# MotherBoard.net
KiCad netlist of a schematic drawn in Altium Designer
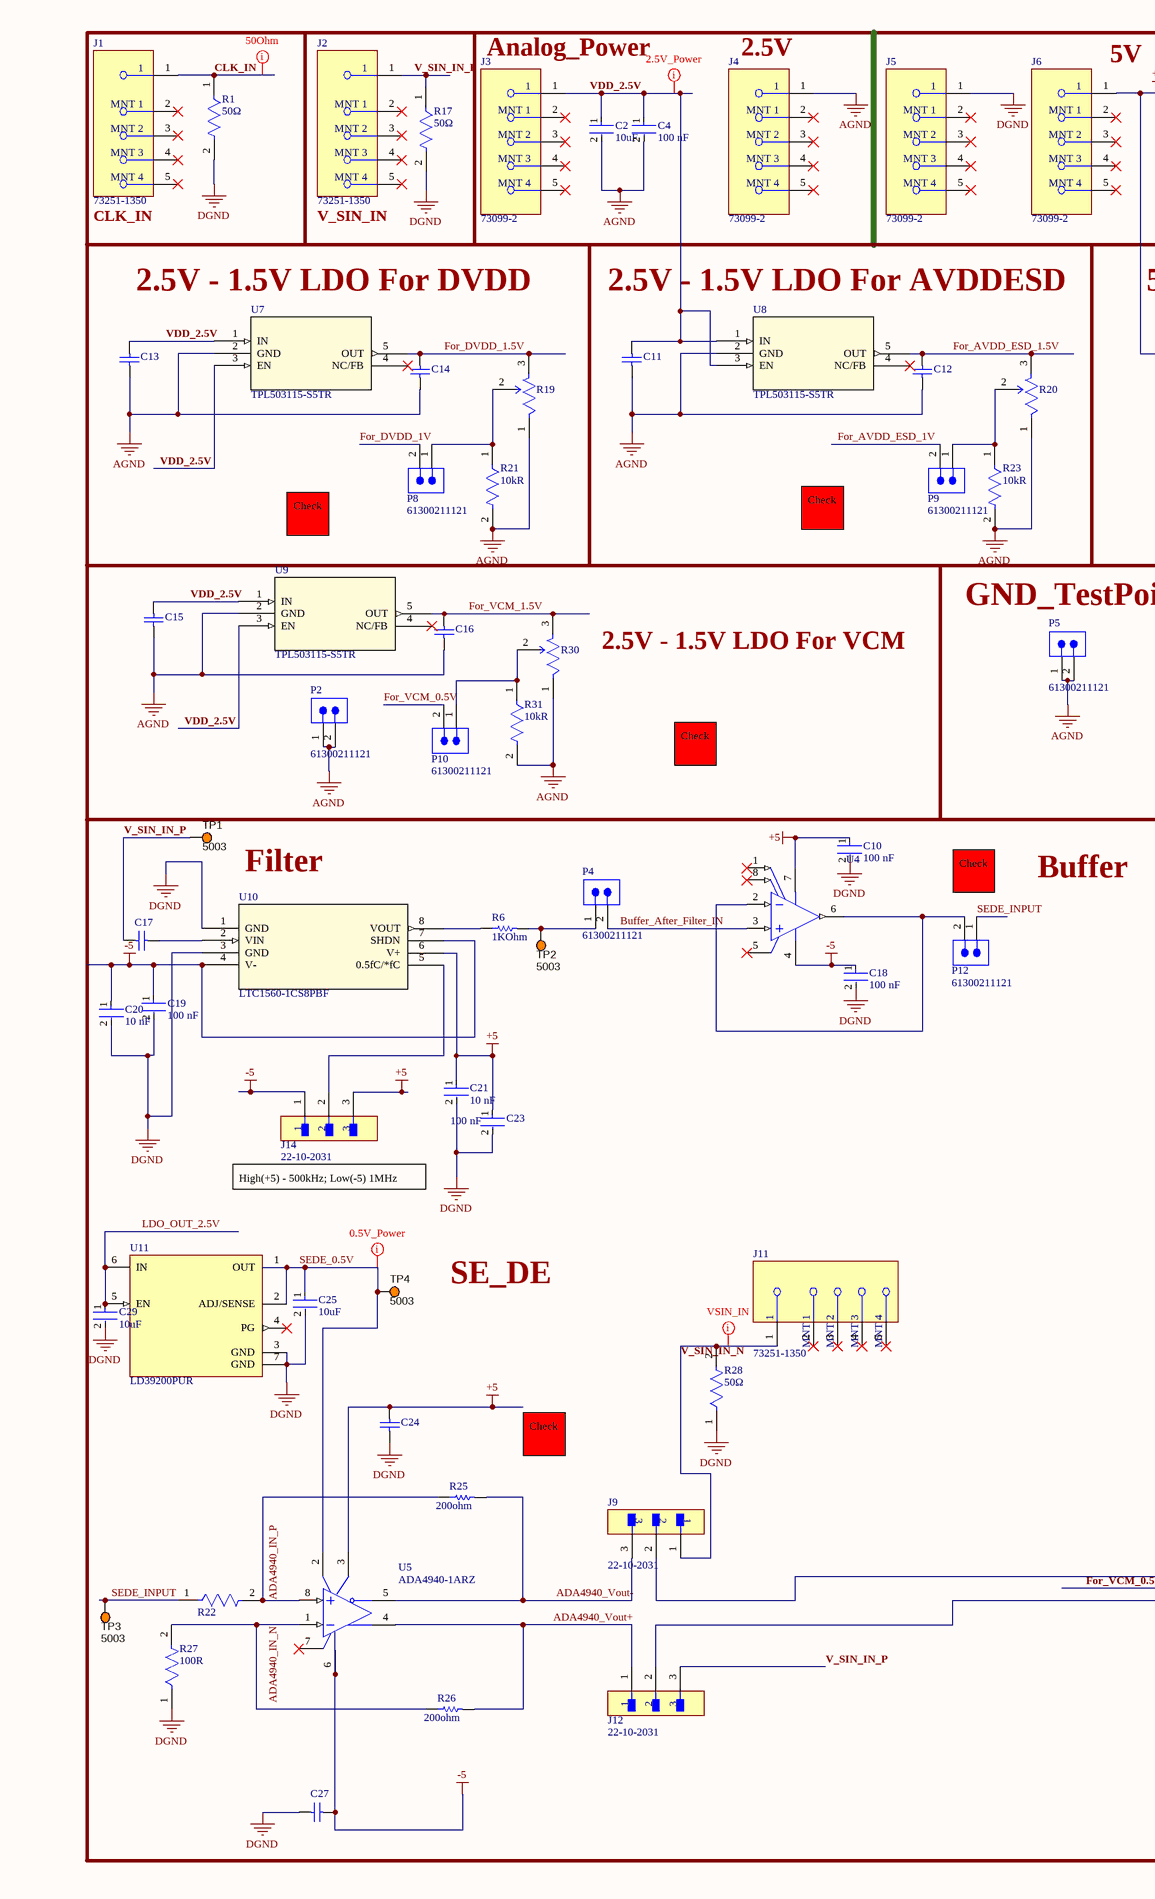
[diagram p0: MotherBoard.SchDoc, left]
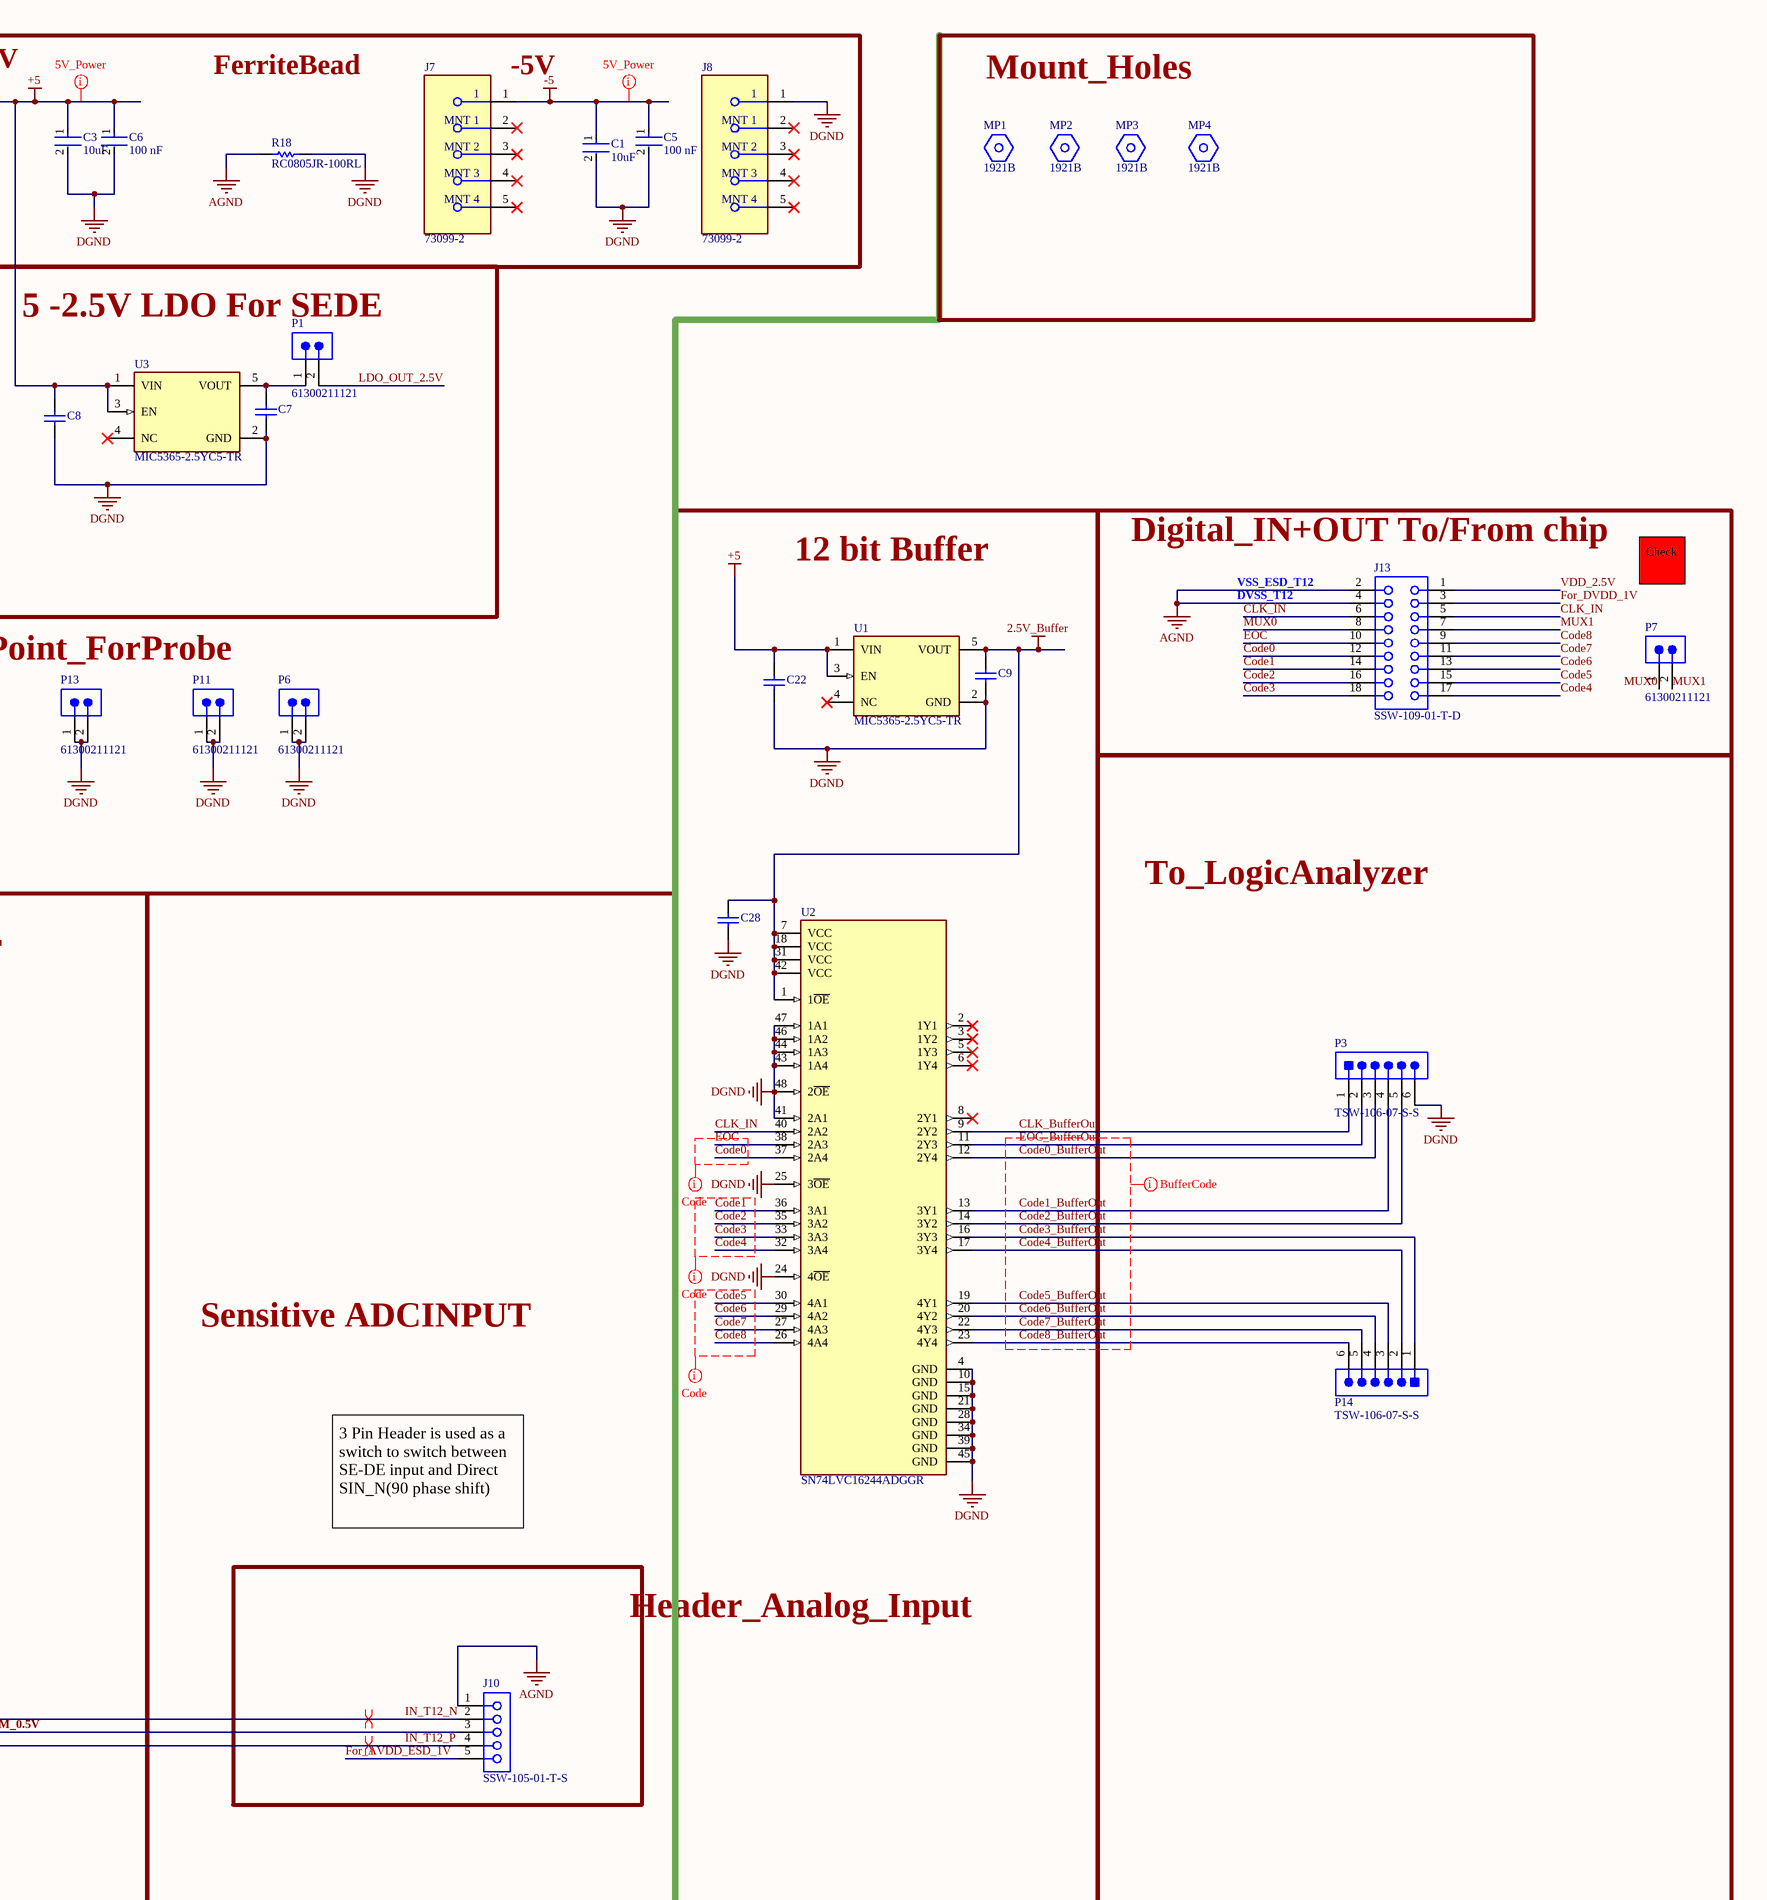
[diagram p1: MotherBoard.SchDoc, right]

(export (version "E")
  (design (tool "Eeschema 10.0.6"))
  (components
    (comp (ref "C1")
      (value "0805ZD106MAT2A")
      (footprint "FP-0805-L_2_01_0_2-W_1_25-MFG")
      (description "General Purpose Ceramic Capacitor, 0805, 10uF, 20%, X5R, 15%, 10V")
      (fields
        (field (name "CAPACITANCE") "10uF")
        (field (name "TOLERANCE") "20%")
        (field (name "VOLTAGE") "10V")
      )
      (libsource (lib "Altium Content Vault") (part "02cd4be3c70576c341d710602a673aa"))
    )
    (comp (ref "C2")
      (value "0805ZD106MAT2A")
      (footprint "FP-0805-L_2_01_0_2-W_1_25-MFG")
      (description "General Purpose Ceramic Capacitor, 0805, 10uF, 20%, X5R, 15%, 10V")
      (fields
        (field (name "CAPACITANCE") "10uF")
        (field (name "TOLERANCE") "20%")
        (field (name "VOLTAGE") "10V")
      )
      (libsource (lib "Altium Content Vault") (part "02cd4be3c70576c341d710602a673aa"))
    )
    (comp (ref "C3")
      (value "0805ZD106MAT2A")
      (footprint "FP-0805-L_2_01_0_2-W_1_25-MFG")
      (description "General Purpose Ceramic Capacitor, 0805, 10uF, 20%, X5R, 15%, 10V")
      (fields
        (field (name "CAPACITANCE") "10uF")
        (field (name "TOLERANCE") "20%")
        (field (name "VOLTAGE") "10V")
      )
      (libsource (lib "Altium Content Vault") (part "02cd4be3c70576c341d710602a673aa"))
    )
    (comp (ref "C4")
      (value "CC0805KRX7R8BB104")
      (footprint "FP-CC0805-0_85-MFG")
      (description "CAP CER 0.1UF 25V X7R 0805")
      (fields
        (field (name "TOLERANCE") "0.1")
        (field (name "MANUFACTURER") "Yageo")
        (field (name "CAPACITANCE") "100 nF")
      )
      (libsource (lib "Altium Content Vault") (part "11868f565c42a9108669ba33697ecf6"))
    )
    (comp (ref "C5")
      (value "CC0805KRX7R8BB104")
      (footprint "FP-CC0805-0_85-MFG")
      (description "CAP CER 0.1UF 25V X7R 0805")
      (fields
        (field (name "TOLERANCE") "0.1")
        (field (name "MANUFACTURER") "Yageo")
        (field (name "CAPACITANCE") "100 nF")
      )
      (libsource (lib "Altium Content Vault") (part "11868f565c42a9108669ba33697ecf6"))
    )
    (comp (ref "C6")
      (value "CC0805KRX7R8BB104")
      (footprint "FP-CC0805-0_85-MFG")
      (description "CAP CER 0.1UF 25V X7R 0805")
      (fields
        (field (name "TOLERANCE") "0.1")
        (field (name "MANUFACTURER") "Yageo")
        (field (name "CAPACITANCE") "100 nF")
      )
      (libsource (lib "Altium Content Vault") (part "11868f565c42a9108669ba33697ecf6"))
    )
    (comp (ref "C7")
      (value "0805ZC105KAZ2A")
      (footprint "CAPC2013X140X50LL20T25")
      (fields (field (name "MANUFACTURER") "AVX Interconnect / Elco"))
      (libsource (lib "Altium Content Vault") (part "CAP"))
    )
    (comp (ref "C8")
      (value "0805ZC105KAZ2A")
      (footprint "CAPC2013X140X50LL20T25")
      (fields (field (name "MANUFACTURER") "AVX Interconnect / Elco"))
      (libsource (lib "Altium Content Vault") (part "CAP"))
    )
    (comp (ref "C9")
      (value "0805ZC105KAZ2A")
      (footprint "CAPC2013X140X50LL20T25")
      (fields (field (name "MANUFACTURER") "AVX Interconnect / Elco"))
      (libsource (lib "Altium Content Vault") (part "CAP"))
    )
    (comp (ref "C10")
      (value "CC0805KRX7R8BB104")
      (footprint "FP-CC0805-0_85-MFG")
      (description "CAP CER 0.1UF 25V X7R 0805")
      (fields
        (field (name "TOLERANCE") "0.1")
        (field (name "MANUFACTURER") "Yageo")
        (field (name "CAPACITANCE") "100 nF")
      )
      (libsource (lib "Altium Content Vault") (part "11868f565c42a9108669ba33697ecf6"))
    )
    (comp (ref "C11")
      (value "0805ZC105KAZ2A")
      (footprint "CAPC2013X140X50LL20T25")
      (fields (field (name "MANUFACTURER") "AVX Interconnect / Elco"))
      (libsource (lib "Altium Content Vault") (part "CAP"))
    )
    (comp (ref "C12")
      (value "0805ZC105KAZ2A")
      (footprint "CAPC2013X140X50LL20T25")
      (fields (field (name "MANUFACTURER") "AVX Interconnect / Elco"))
      (libsource (lib "Altium Content Vault") (part "CAP"))
    )
    (comp (ref "C13")
      (value "0805ZC105KAZ2A")
      (footprint "CAPC2013X140X50LL20T25")
      (fields (field (name "MANUFACTURER") "AVX Interconnect / Elco"))
      (libsource (lib "Altium Content Vault") (part "CAP"))
    )
    (comp (ref "C14")
      (value "0805ZC105KAZ2A")
      (footprint "CAPC2013X140X50LL20T25")
      (fields (field (name "MANUFACTURER") "AVX Interconnect / Elco"))
      (libsource (lib "Altium Content Vault") (part "CAP"))
    )
    (comp (ref "C15")
      (value "0805ZC105KAZ2A")
      (footprint "CAPC2013X140X50LL20T25")
      (fields (field (name "MANUFACTURER") "AVX Interconnect / Elco"))
      (libsource (lib "Altium Content Vault") (part "CAP"))
    )
    (comp (ref "C16")
      (value "0805ZC105KAZ2A")
      (footprint "CAPC2013X140X50LL20T25")
      (fields (field (name "MANUFACTURER") "AVX Interconnect / Elco"))
      (libsource (lib "Altium Content Vault") (part "CAP"))
    )
    (comp (ref "C17")
      (value "VJ0805D561KXBAJ")
      (footprint "CAPC2013X145X48ML20T23")
      (fields (field (name "MANUFACTURER") "Vitramon"))
      (libsource (lib "Altium Content Vault") (part "CAP"))
    )
    (comp (ref "C18")
      (value "CC0805KRX7R8BB104")
      (footprint "FP-CC0805-0_85-MFG")
      (description "CAP CER 0.1UF 25V X7R 0805")
      (fields
        (field (name "TOLERANCE") "0.1")
        (field (name "MANUFACTURER") "Yageo")
        (field (name "CAPACITANCE") "100 nF")
      )
      (libsource (lib "Altium Content Vault") (part "11868f565c42a9108669ba33697ecf6"))
    )
    (comp (ref "C19")
      (value "CC0805KRX7R8BB104")
      (footprint "FP-CC0805-0_85-MFG")
      (description "CAP CER 0.1UF 25V X7R 0805")
      (fields
        (field (name "TOLERANCE") "0.1")
        (field (name "MANUFACTURER") "Yageo")
        (field (name "CAPACITANCE") "100 nF")
      )
      (libsource (lib "Altium Content Vault") (part "11868f565c42a9108669ba33697ecf6"))
    )
    (comp (ref "C20")
      (value "CC0805KRX7R9BB103")
      (footprint "FP-CC0805-0_85-MFG")
      (description "CAP CER 10000PF 50V X7R 0805")
      (fields
        (field (name "CAPACITANCE") "10 nF")
        (field (name "OCTOPART") "https://octopart.com/cc0805krx7r9bb103-yageo-192989")
        (field (name "MANUFACTURER") "Yageo")
      )
      (libsource (lib "Altium Content Vault") (part "11868f565c42a9108669ba33697ecf6"))
    )
    (comp (ref "C21")
      (value "CC0805KRX7R9BB103")
      (footprint "FP-CC0805-0_85-MFG")
      (description "CAP CER 10000PF 50V X7R 0805")
      (fields
        (field (name "CAPACITANCE") "10 nF")
        (field (name "OCTOPART") "https://octopart.com/cc0805krx7r9bb103-yageo-192989")
        (field (name "MANUFACTURER") "Yageo")
      )
      (libsource (lib "Altium Content Vault") (part "11868f565c42a9108669ba33697ecf6"))
    )
    (comp (ref "C22")
      (value "0805ZC105KAZ2A")
      (footprint "CAPC2013X140X50LL20T25")
      (fields (field (name "MANUFACTURER") "AVX Interconnect / Elco"))
      (libsource (lib "Altium Content Vault") (part "CAP"))
    )
    (comp (ref "C23")
      (value "CC0805KRX7R8BB104")
      (footprint "FP-CC0805-0_85-MFG")
      (description "CAP CER 0.1UF 25V X7R 0805")
      (fields
        (field (name "TOLERANCE") "0.1")
        (field (name "MANUFACTURER") "Yageo")
        (field (name "CAPACITANCE") "100 nF")
      )
      (libsource (lib "Altium Content Vault") (part "11868f565c42a9108669ba33697ecf6"))
    )
    (comp (ref "C24")
      (value "0805ZC105KAZ2A")
      (footprint "CAPC2013X140X50LL20T25")
      (fields (field (name "MANUFACTURER") "AVX Interconnect / Elco"))
      (libsource (lib "Altium Content Vault") (part "CAP"))
    )
    (comp (ref "C25")
      (value "0805ZD106MAT2A")
      (footprint "FP-0805-L_2_01_0_2-W_1_25-MFG")
      (description "General Purpose Ceramic Capacitor, 0805, 10uF, 20%, X5R, 15%, 10V")
      (fields
        (field (name "CAPACITANCE") "10uF")
        (field (name "TOLERANCE") "20%")
        (field (name "VOLTAGE") "10V")
      )
      (libsource (lib "Altium Content Vault") (part "02cd4be3c70576c341d710602a673aa"))
    )
    (comp (ref "C27")
      (value "0805ZC105KAZ2A")
      (footprint "CAPC2013X140X50LL20T25")
      (fields (field (name "MANUFACTURER") "AVX Interconnect / Elco"))
      (libsource (lib "Altium Content Vault") (part "CAP"))
    )
    (comp (ref "C28")
      (value "0805ZC105KAZ2A")
      (footprint "CAPC2013X140X50LL20T25")
      (fields (field (name "MANUFACTURER") "AVX Interconnect / Elco"))
      (libsource (lib "Altium Content Vault") (part "CAP"))
    )
    (comp (ref "C29")
      (value "0805ZD106MAT2A")
      (footprint "FP-0805-L_2_01_0_2-W_1_25-MFG")
      (description "General Purpose Ceramic Capacitor, 0805, 10uF, 20%, X5R, 15%, 10V")
      (fields
        (field (name "CAPACITANCE") "10uF")
        (field (name "TOLERANCE") "20%")
        (field (name "VOLTAGE") "10V")
      )
      (libsource (lib "Altium Content Vault") (part "02cd4be3c70576c341d710602a673aa"))
    )
    (comp (ref "J1")
      (value "73251-1350")
      (footprint "FP-73251-1350-MFG")
      (description "CONN SMA JACK STR 50 OHM SMD")
      (fields
        (field (name "OCTOPART") "https://octopart.com/73251-1350-molex-5414390")
        (field (name "MANUFACTURER") "Molex")
      )
      (libsource (lib "") (part "474d33b8a96b1ade9ed6dd87a2b06d4_1"))
    )
    (comp (ref "J2")
      (value "73251-1350")
      (footprint "FP-73251-1350-MFG")
      (description "CONN SMA JACK STR 50 OHM SMD")
      (fields
        (field (name "OCTOPART") "https://octopart.com/73251-1350-molex-5414390")
        (field (name "MANUFACTURER") "Molex")
      )
      (libsource (lib "") (part "474d33b8a96b1ade9ed6dd87a2b06d4_1"))
    )
    (comp (ref "J3")
      (value "73099-2")
      (footprint "FP-73099-2-MFG")
      (description "R/A 4MM MOUNTG SAFE JACK/PCB RED")
      (libsource (lib "Altium Content Vault") (part "9c40ac4d87bbbe9fcb330bd20f98ca3"))
    )
    (comp (ref "J4")
      (value "73099-2")
      (footprint "FP-73099-2-MFG")
      (description "R/A 4MM MOUNTG SAFE JACK/PCB RED")
      (libsource (lib "Altium Content Vault") (part "9c40ac4d87bbbe9fcb330bd20f98ca3"))
    )
    (comp (ref "J5")
      (value "73099-2")
      (footprint "FP-73099-2-MFG")
      (description "R/A 4MM MOUNTG SAFE JACK/PCB RED")
      (libsource (lib "Altium Content Vault") (part "9c40ac4d87bbbe9fcb330bd20f98ca3"))
    )
    (comp (ref "J6")
      (value "73099-2")
      (footprint "FP-73099-2-MFG")
      (description "R/A 4MM MOUNTG SAFE JACK/PCB RED")
      (libsource (lib "Altium Content Vault") (part "9c40ac4d87bbbe9fcb330bd20f98ca3"))
    )
    (comp (ref "J7")
      (value "73099-2")
      (footprint "FP-73099-2-MFG")
      (description "R/A 4MM MOUNTG SAFE JACK/PCB RED")
      (libsource (lib "Altium Content Vault") (part "9c40ac4d87bbbe9fcb330bd20f98ca3"))
    )
    (comp (ref "J8")
      (value "73099-2")
      (footprint "FP-73099-2-MFG")
      (description "R/A 4MM MOUNTG SAFE JACK/PCB RED")
      (libsource (lib "Altium Content Vault") (part "9c40ac4d87bbbe9fcb330bd20f98ca3"))
    )
    (comp (ref "J9")
      (value "22-10-2031")
      (footprint "FP-22-10-2031-MFG")
      (description "CONN HEADER VERT 3POS 2.54MM")
      (libsource (lib "Altium Content Vault") (part "0d3f023dd272f625e17a2be33dea85f"))
    )
    (comp (ref "J10")
      (value "SSW-105-01-T-S")
      (footprint "SMTC-SSW-105-01-X-S")
      (description "SQ Post Socket, Through-hole, Vertical, -55 to 105 degC, 2.54mm Pitch, 5-Pin, Female, RoHS")
      (fields (field (name "MANUFACTURER") "Samtec"))
      (libsource (lib "Altium Content Vault") (part "SMTC-SSW-105-X-X-S"))
    )
    (comp (ref "J11")
      (value "73251-1350")
      (footprint "FP-73251-1350-MFG")
      (description "CONN SMA JACK STR 50 OHM SMD")
      (fields
        (field (name "OCTOPART") "https://octopart.com/73251-1350-molex-5414390")
        (field (name "MANUFACTURER") "Molex")
      )
      (libsource (lib "Altium Content Vault") (part "474d33b8a96b1ade9ed6dd87a2b06d4"))
    )
    (comp (ref "J12")
      (value "22-10-2031")
      (footprint "FP-22-10-2031-MFG")
      (description "CONN HEADER VERT 3POS 2.54MM")
      (libsource (lib "") (part "0d3f023dd272f625e17a2be33dea85f_1"))
    )
    (comp (ref "J13")
      (value "SSW-109-01-T-D")
      (footprint "SMTC-SSW-109-01-X-D")
      (description "SQ Post Socket, Through-hole, Vertical, -55 to 105 degC, 2.54mm Pitch, 18-Pin, Female, RoHS")
      (fields (field (name "MANUFACTURER") "Samtec"))
      (libsource (lib "Altium Content Vault") (part "SMTC-SSW-109-01-X-D"))
    )
    (comp (ref "J14")
      (value "22-10-2031")
      (footprint "FP-22-10-2031-MFG")
      (description "CONN HEADER VERT 3POS 2.54MM")
      (libsource (lib "") (part "0d3f023dd272f625e17a2be33dea85f_1"))
    )
    (comp (ref "MP1")
      (value "1921B")
      (footprint "FP-1921B-MFG")
      (description "1921B Standoff, 1/4 Hex, Female, Threaded 4-40, Length .500, Stainless Steel")
      (libsource (lib "Altium Content Vault") (part "08a03163f22740170b61ca9211e1d1e"))
    )
    (comp (ref "MP2")
      (value "1921B")
      (footprint "FP-1921B-MFG")
      (description "1921B Standoff, 1/4 Hex, Female, Threaded 4-40, Length .500, Stainless Steel")
      (libsource (lib "Altium Content Vault") (part "08a03163f22740170b61ca9211e1d1e"))
    )
    (comp (ref "MP3")
      (value "1921B")
      (footprint "FP-1921B-MFG")
      (description "1921B Standoff, 1/4 Hex, Female, Threaded 4-40, Length .500, Stainless Steel")
      (libsource (lib "Altium Content Vault") (part "08a03163f22740170b61ca9211e1d1e"))
    )
    (comp (ref "MP4")
      (value "1921B")
      (footprint "FP-1921B-MFG")
      (description "1921B Standoff, 1/4 Hex, Female, Threaded 4-40, Length .500, Stainless Steel")
      (libsource (lib "Altium Content Vault") (part "08a03163f22740170b61ca9211e1d1e"))
    )
    (comp (ref "P1")
      (value "61300211121")
      (footprint "61300211121")
      (libsource (lib "Altium Content Vault") (part "Header_Male_1R_02P"))
    )
    (comp (ref "P2")
      (value "61300211121")
      (footprint "61300211121")
      (libsource (lib "Altium Content Vault") (part "Header_Male_1R_02P"))
    )
    (comp (ref "P3")
      (value "TSW-106-07-S-S")
      (footprint "SMTC-TSW-106-07-S-S_V")
      (fields (field (name "MANUFACTURER") "Samtec"))
      (libsource (lib "Altium Content Vault") (part "CN-1P-M-R6"))
    )
    (comp (ref "P4")
      (value "61300211121")
      (footprint "61300211121")
      (libsource (lib "Altium Content Vault") (part "Header_Male_1R_02P"))
    )
    (comp (ref "P5")
      (value "61300211121")
      (footprint "61300211121")
      (libsource (lib "Altium Content Vault") (part "Header_Male_1R_02P"))
    )
    (comp (ref "P6")
      (value "61300211121")
      (footprint "61300211121")
      (libsource (lib "Altium Content Vault") (part "Header_Male_1R_02P"))
    )
    (comp (ref "P7")
      (value "61300211121")
      (footprint "61300211121")
      (libsource (lib "Altium Content Vault") (part "Header_Male_1R_02P"))
    )
    (comp (ref "P8")
      (value "61300211121")
      (footprint "61300211121")
      (libsource (lib "Altium Content Vault") (part "Header_Male_1R_02P"))
    )
    (comp (ref "P9")
      (value "61300211121")
      (footprint "61300211121")
      (libsource (lib "Altium Content Vault") (part "Header_Male_1R_02P"))
    )
    (comp (ref "P10")
      (value "61300211121")
      (footprint "61300211121")
      (libsource (lib "Altium Content Vault") (part "Header_Male_1R_02P"))
    )
    (comp (ref "P11")
      (value "61300211121")
      (footprint "61300211121")
      (libsource (lib "Altium Content Vault") (part "Header_Male_1R_02P"))
    )
    (comp (ref "P12")
      (value "61300211121")
      (footprint "61300211121")
      (libsource (lib "Altium Content Vault") (part "Header_Male_1R_02P"))
    )
    (comp (ref "P13")
      (value "61300211121")
      (footprint "61300211121")
      (libsource (lib "Altium Content Vault") (part "Header_Male_1R_02P"))
    )
    (comp (ref "P14")
      (value "TSW-106-07-S-S")
      (footprint "SMTC-TSW-106-07-S-S_V")
      (fields (field (name "MANUFACTURER") "Samtec"))
      (libsource (lib "") (part "CN-1P-M-R6_1"))
    )
    (comp (ref "R1")
      (value "CRCW080550R0FKTA")
      (footprint "FP-D12-CRCW0805-MFG")
      (description "CRCW080550R0FKTA Res Thick Film 0805 50 Ohm 1% 0.125W(1/8W) ±100ppm/C Pad SMD Automotive T/R")
      (fields (field (name "TOLERANCE") "1%") (field (name "RESISTANCE") "50Ω"))
      (libsource (lib "Altium Content Vault") (part "1029c3af85768c4190bb7ad29bc67b5"))
    )
    (comp (ref "R6")
      (value "RC0805FR-071KL")
      (footprint "RESC2013X60X35ML10T20")
      (description "Chip Resistor, 1 KOhm, +/- 1%, 125 mW, -55 to 155 degC, 0805 (2012 Metric), RoHS, Tape and Reel")
      (fields
        (field (name "RESISTANCE") "1KOhm")
        (field (name "TOLERANCE") "1%")
        (field (name "MANUFACTURER") "Yageo")
      )
      (libsource (lib "Altium Content Vault") (part "RES-2"))
    )
    (comp (ref "R17")
      (value "CRCW080550R0FKTA")
      (footprint "FP-D12-CRCW0805-MFG")
      (description "CRCW080550R0FKTA Res Thick Film 0805 50 Ohm 1% 0.125W(1/8W) ±100ppm/C Pad SMD Automotive T/R")
      (fields (field (name "TOLERANCE") "1%") (field (name "RESISTANCE") "50Ω"))
      (libsource (lib "Altium Content Vault") (part "1029c3af85768c4190bb7ad29bc67b5"))
    )
    (comp (ref "R18")
      (value "RC0805JR-100RL")
      (footprint "RESC2013X60X35LL10T20")
      (description "Chip Resistor, 0 Ohm, +/- 5%, 125 mW, -55 to 155 degC, 0805 (2012 Metric), RoHS, Tape and Reel")
      (fields (field (name "MANUFACTURER") "Yageo"))
      (libsource (lib "Altium Content Vault") (part "RES-2"))
    )
    (comp (ref "R19")
      (value "3296W-1-253LF")
      (footprint "FP-3296W-MFG")
      (description "TRIMMER 25K OHM 0.5W PC PIN TOP")
      (fields (field (name "TOLERANCE") "10%"))
      (libsource (lib "Altium Content Vault") (part "2dcfd2547301a7d3209a5e99acfd772"))
    )
    (comp (ref "R20")
      (value "3296W-1-253LF")
      (footprint "FP-3296W-MFG")
      (description "TRIMMER 25K OHM 0.5W PC PIN TOP")
      (fields (field (name "TOLERANCE") "10%"))
      (libsource (lib "Altium Content Vault") (part "2dcfd2547301a7d3209a5e99acfd772"))
    )
    (comp (ref "R21")
      (value "CRCW080510K0FKEA")
      (footprint "FP-CRCW0805-e3-IPC_A")
      (description "RES Thick Film, 10kΩ, 1%, 0.125W, 100ppm/°C, 0805")
      (fields (field (name "RESISTANCE") "10kR") (field (name "TOLERANCE") "1%"))
      (libsource (lib "Altium Content Vault") (part "1029c3af85768c4190bb7ad29bc67b5"))
    )
    (comp (ref "R22")
      (value "CRCW0805100RFKEAHP")
      (footprint "FP-CRCW0805-HPe3-IPC_A")
      (description "RES Thick Film, 100Ω, 1%, 0.5W, 100ppm/°C, 0805")
      (fields (field (name "TOLERANCE") "1%"))
      (libsource (lib "Altium Content Vault") (part "1029c3af85768c4190bb7ad29bc67b5"))
    )
    (comp (ref "R23")
      (value "CRCW080510K0FKEA")
      (footprint "FP-CRCW0805-e3-IPC_A")
      (description "RES Thick Film, 10kΩ, 1%, 0.125W, 100ppm/°C, 0805")
      (fields (field (name "RESISTANCE") "10kR") (field (name "TOLERANCE") "1%"))
      (libsource (lib "Altium Content Vault") (part "1029c3af85768c4190bb7ad29bc67b5"))
    )
    (comp (ref "R25")
      (value "200ohm")
      (footprint "RESC2013X70X40ML20T20")
      (fields (field (name "MANUFACTURER") "Panasonic") (field (name "PART NUMBER") "ERJ-6ENF2000V"))
      (libsource (lib "Altium Content Vault") (part "RES"))
    )
    (comp (ref "R26")
      (value "200ohm")
      (footprint "RESC2013X70X40ML20T20")
      (fields (field (name "MANUFACTURER") "Panasonic") (field (name "PART NUMBER") "ERJ-6ENF2000V"))
      (libsource (lib "Altium Content Vault") (part "RES"))
    )
    (comp (ref "R27")
      (value "CRCW0805100RFKEAHP")
      (footprint "FP-CRCW0805-HPe3-IPC_A")
      (description "RES Thick Film, 100Ω, 1%, 0.5W, 100ppm/°C, 0805")
      (fields (field (name "TOLERANCE") "1%") (field (name "RESISTANCE") "100R"))
      (libsource (lib "Altium Content Vault") (part "1029c3af85768c4190bb7ad29bc67b5"))
    )
    (comp (ref "R28")
      (value "CRCW080550R0FKTA")
      (footprint "FP-D12-CRCW0805-MFG")
      (description "CRCW080550R0FKTA Res Thick Film 0805 50 Ohm 1% 0.125W(1/8W) ±100ppm/C Pad SMD Automotive T/R")
      (fields (field (name "TOLERANCE") "1%") (field (name "RESISTANCE") "50Ω"))
      (libsource (lib "Altium Content Vault") (part "1029c3af85768c4190bb7ad29bc67b5"))
    )
    (comp (ref "R30")
      (value "3296W-1-253LF")
      (footprint "FP-3296W-MFG")
      (description "TRIMMER 25K OHM 0.5W PC PIN TOP")
      (fields (field (name "TOLERANCE") "10%"))
      (libsource (lib "Altium Content Vault") (part "2dcfd2547301a7d3209a5e99acfd772"))
    )
    (comp (ref "R31")
      (value "CRCW080510K0FKEA")
      (footprint "FP-CRCW0805-e3-IPC_A")
      (description "RES Thick Film, 10kΩ, 1%, 0.125W, 100ppm/°C, 0805")
      (fields (field (name "RESISTANCE") "10kR") (field (name "TOLERANCE") "1%"))
      (libsource (lib "Altium Content Vault") (part "1029c3af85768c4190bb7ad29bc67b5"))
    )
    (comp (ref "TP1")
      (value "5003")
      (footprint "KSTN-5003")
      (description "Test Point, Orange, 1-Pin THD, RoHS")
      (libsource (lib "Altium Content Vault") (part "TESTPOINT_ORANGE"))
    )
    (comp (ref "TP2")
      (value "5003")
      (footprint "KSTN-5003")
      (description "Test Point, Orange, 1-Pin THD, RoHS")
      (libsource (lib "Altium Content Vault") (part "TESTPOINT_ORANGE"))
    )
    (comp (ref "TP3")
      (value "5003")
      (footprint "KSTN-5003")
      (description "Test Point, Orange, 1-Pin THD, RoHS")
      (libsource (lib "Altium Content Vault") (part "TESTPOINT_ORANGE"))
    )
    (comp (ref "TP4")
      (value "5003")
      (footprint "KSTN-5003")
      (description "Test Point, Orange, 1-Pin THD, RoHS")
      (libsource (lib "Altium Content Vault") (part "TESTPOINT_ORANGE"))
    )
    (comp (ref "U1")
      (value "MIC5365-2.5YC5-TR")
      (footprint "FP-SC70-5LD-PL-1-MFG")
      (description "IC REG LINEAR 2.5V 150MA SC70-5")
      (libsource (lib "Altium Content Vault") (part "62bd28826b54e3bd5f89c9ba9bda61c"))
    )
    (comp (ref "U2")
      (value "SN74LVC16244ADGGR")
      (footprint "FP-DGG0048A-IPC_B")
      (description "IC BUF NON-INVERT 3.6V 48TSSOP")
      (libsource (lib "Altium Content Vault") (part "34c0b7439352cfd7100edb36af6fd87"))
    )
    (comp (ref "U3")
      (value "MIC5365-2.5YC5-TR")
      (footprint "FP-SC70-5LD-PL-1-MFG")
      (description "IC REG LINEAR 2.5V 150MA SC70-5")
      (libsource (lib "Altium Content Vault") (part "62bd28826b54e3bd5f89c9ba9bda61c"))
    )
    (comp (ref "U4")
      (value "LT1360CS8#PBF")
      (footprint "LT-S8-8_L")
      (fields
        (field (name "LINEAR TECHNOLOGY PART NUMBER") "LT1360")
        (field (name "MANUFACTURER") "Linear Technology")
      )
      (libsource (lib "Altium Content Vault") (part "LT-LT135X-LT136X-8"))
    )
    (comp (ref "U5")
      (value "ADA4940-1ARZ")
      (footprint "ADI-R-8_L")
      (libsource (lib "Altium Content Vault") (part "ADI-ADA4940-R-8"))
    )
    (comp (ref "U7")
      (value "TPL503115-S5TR")
      (footprint "SOT23-5-A_TPK")
      (description "No Description Available")
      (libsource (lib "TPL503115-S5TR") (part "TPL503115-S5TR"))
    )
    (comp (ref "U8")
      (value "TPL503115-S5TR")
      (footprint "SOT23-5-A_TPK")
      (description "No Description Available")
      (libsource (lib "TPL503115-S5TR") (part "TPL503115-S5TR"))
    )
    (comp (ref "U9")
      (value "TPL503115-S5TR")
      (footprint "SOT23-5-A_TPK")
      (description "No Description Available")
      (libsource (lib "TPL503115-S5TR") (part "TPL503115-S5TR"))
    )
    (comp (ref "U10")
      (value "LTC1560-1CS8PBF")
      (footprint "SO-8_S_LIT-M")
      (description "No Description Available")
      (libsource (lib "LTC1560-1CS8PBF") (part "LTC1560-1CS8PBF"))
    )
    (comp (ref "U11")
      (value "LD39200PUR")
      (footprint "FP-DFN6-7946637-IPC_A")
      (description "IC REG LINEAR POS ADJ 2A 6DFN")
      (fields
        (field (name "MANUFACTURER") "STMicroelectronics")
        (field (name "OCTOPART") "https://octopart.com/ld39200pur-stmicroelectronics-77085816")
      )
      (libsource (lib "Altium Content Vault") (part "edb6347640e7083f10f76e8a04eaca8"))
    )
  )
  (nets
    (net (code "1") (name "+5") (class "Default")
      (node (ref "C10") (pin "1") (pinfunction "1_1") (pintype "passive"))
      (node (ref "C21") (pin "1") (pinfunction "1_1") (pintype "passive"))
      (node (ref "C22") (pin "2") (pinfunction "2_2") (pintype "passive"))
      (node (ref "C23") (pin "1") (pinfunction "1_1") (pintype "passive"))
      (node (ref "C24") (pin "2") (pinfunction "2_2") (pintype "passive"))
      (node (ref "C3") (pin "1") (pinfunction "1_1") (pintype "passive"))
      (node (ref "C6") (pin "1") (pinfunction "1_1") (pintype "passive"))
      (node (ref "C8") (pin "2") (pinfunction "2_2") (pintype "passive"))
      (node (ref "J14") (pin "3") (pinfunction "3_3") (pintype "passive"))
      (node (ref "J6") (pin "1") (pinfunction "1_1") (pintype "passive"))
      (node (ref "U1") (pin "1") (pinfunction "VIN_1") (pintype "power_in"))
      (node (ref "U1") (pin "3") (pinfunction "EN_3") (pintype "input"))
      (node (ref "U10") (pin "6") (pinfunction "V+_6") (pintype "power_in"))
      (node (ref "U3") (pin "1") (pinfunction "VIN_1") (pintype "power_in"))
      (node (ref "U3") (pin "3") (pinfunction "EN_3") (pintype "input"))
      (node (ref "U4") (pin "7") (pinfunction "V+_7") (pintype "power_in"))
      (node (ref "U5") (pin "3") (pinfunction "VS+_3") (pintype "power_in"))
    )
    (net (code "2") (name "-5") (class "Default")
      (node (ref "C1") (pin "1") (pinfunction "1_1") (pintype "passive"))
      (node (ref "C18") (pin "1") (pinfunction "1_1") (pintype "passive"))
      (node (ref "C19") (pin "1") (pinfunction "1_1") (pintype "passive"))
      (node (ref "C20") (pin "1") (pinfunction "1_1") (pintype "passive"))
      (node (ref "C27") (pin "2") (pinfunction "2_2") (pintype "passive"))
      (node (ref "C5") (pin "1") (pinfunction "1_1") (pintype "passive"))
      (node (ref "J14") (pin "1") (pinfunction "1_1") (pintype "passive"))
      (node (ref "J7") (pin "1") (pinfunction "1_1") (pintype "passive"))
      (node (ref "U10") (pin "4") (pinfunction "V-_4") (pintype "power_in"))
      (node (ref "U10") (pin "7") (pinfunction "SHDN_7") (pintype "passive"))
      (node (ref "U4") (pin "4") (pinfunction "V-_4") (pintype "power_in"))
      (node (ref "U5") (pin "6") (pinfunction "VS-_6") (pintype "power_in"))
    )
    (net (code "3") (name "/ADA4940_IN_N") (class "Default")
      (node (ref "R26") (pin "1") (pinfunction "1_1") (pintype "passive"))
      (node (ref "R27") (pin "2") (pinfunction "2_2") (pintype "passive"))
      (node (ref "U5") (pin "1") (pinfunction "IN-_1") (pintype "input"))
    )
    (net (code "4") (name "/ADA4940_IN_P") (class "Default")
      (node (ref "R22") (pin "2") (pinfunction "2_2") (pintype "passive"))
      (node (ref "R25") (pin "1") (pinfunction "1_1") (pintype "passive"))
      (node (ref "U5") (pin "8") (pinfunction "IN+_8") (pintype "input"))
    )
    (net (code "5") (name "/ADA4940_Vout+") (class "Default")
      (node (ref "J12") (pin "1") (pinfunction "1_1") (pintype "passive"))
      (node (ref "R26") (pin "2") (pinfunction "2_2") (pintype "passive"))
      (node (ref "U5") (pin "4") (pinfunction "OUT+_4") (pintype "tri_state"))
    )
    (net (code "6") (name "/ADA4940_Vout-") (class "Default")
      (node (ref "J9") (pin "3") (pinfunction "3_3") (pintype "passive"))
      (node (ref "R25") (pin "2") (pinfunction "2_2") (pintype "passive"))
      (node (ref "U5") (pin "5") (pinfunction "OUT-_5") (pintype "tri_state"))
    )
    (net (code "7") (name "/Buffer_After_Filter_IN") (class "Default")
      (node (ref "P4") (pin "2") (pinfunction "2_2") (pintype "passive"))
      (node (ref "U4") (pin "3") (pinfunction "+IN_3") (pintype "input"))
    )
    (net (code "8") (name "/CLK_BufferOut") (class "Default")
      (node (ref "P3") (pin "1") (pinfunction "1_1") (pintype "passive"))
      (node (ref "U2") (pin "9") (pinfunction "2Y2_9") (pintype "output"))
    )
    (net (code "9") (name "/CLK_IN") (class "Default")
      (node (ref "J1") (pin "1") (pinfunction "1_1") (pintype "passive"))
      (node (ref "J13") (pin "5") (pinfunction "5_5") (pintype "passive"))
      (node (ref "J13") (pin "6") (pinfunction "6_6") (pintype "passive"))
      (node (ref "R1") (pin "1") (pinfunction "1_1") (pintype "passive"))
      (node (ref "U2") (pin "40") (pinfunction "2A2_40") (pintype "input"))
    )
    (net (code "10") (name "/Code0") (class "Default")
      (node (ref "J13") (pin "12") (pinfunction "12_12") (pintype "passive"))
      (node (ref "U2") (pin "37") (pinfunction "2A4_37") (pintype "input"))
    )
    (net (code "11") (name "/Code0_BufferOut") (class "Default")
      (node (ref "P3") (pin "3") (pinfunction "3_3") (pintype "passive"))
      (node (ref "U2") (pin "12") (pinfunction "2Y4_12") (pintype "output"))
    )
    (net (code "12") (name "/Code1") (class "Default")
      (node (ref "J13") (pin "14") (pinfunction "14_14") (pintype "passive"))
      (node (ref "U2") (pin "36") (pinfunction "3A1_36") (pintype "input"))
    )
    (net (code "13") (name "/Code1_BufferOut") (class "Default")
      (node (ref "P3") (pin "4") (pinfunction "4_4") (pintype "passive"))
      (node (ref "U2") (pin "13") (pinfunction "3Y1_13") (pintype "output"))
    )
    (net (code "14") (name "/Code2") (class "Default")
      (node (ref "J13") (pin "16") (pinfunction "16_16") (pintype "passive"))
      (node (ref "U2") (pin "35") (pinfunction "3A2_35") (pintype "input"))
    )
    (net (code "15") (name "/Code2_BufferOut") (class "Default")
      (node (ref "P3") (pin "5") (pinfunction "5_5") (pintype "passive"))
      (node (ref "U2") (pin "14") (pinfunction "3Y2_14") (pintype "output"))
    )
    (net (code "16") (name "/Code3") (class "Default")
      (node (ref "J13") (pin "18") (pinfunction "18_18") (pintype "passive"))
      (node (ref "U2") (pin "33") (pinfunction "3A3_33") (pintype "input"))
    )
    (net (code "17") (name "/Code3_BufferOut") (class "Default")
      (node (ref "P14") (pin "1") (pinfunction "1_1") (pintype "passive"))
      (node (ref "U2") (pin "16") (pinfunction "3Y3_16") (pintype "output"))
    )
    (net (code "18") (name "/Code4") (class "Default")
      (node (ref "J13") (pin "17") (pinfunction "17_17") (pintype "passive"))
      (node (ref "U2") (pin "32") (pinfunction "3A4_32") (pintype "input"))
    )
    (net (code "19") (name "/Code4_BufferOut") (class "Default")
      (node (ref "P14") (pin "2") (pinfunction "2_2") (pintype "passive"))
      (node (ref "U2") (pin "17") (pinfunction "3Y4_17") (pintype "output"))
    )
    (net (code "20") (name "/Code5") (class "Default")
      (node (ref "J13") (pin "15") (pinfunction "15_15") (pintype "passive"))
      (node (ref "U2") (pin "30") (pinfunction "4A1_30") (pintype "input"))
    )
    (net (code "21") (name "/Code5_BufferOut") (class "Default")
      (node (ref "P14") (pin "3") (pinfunction "3_3") (pintype "passive"))
      (node (ref "U2") (pin "19") (pinfunction "4Y1_19") (pintype "output"))
    )
    (net (code "22") (name "/Code6") (class "Default")
      (node (ref "J13") (pin "13") (pinfunction "13_13") (pintype "passive"))
      (node (ref "U2") (pin "29") (pinfunction "4A2_29") (pintype "input"))
    )
    (net (code "23") (name "/Code6_BufferOut") (class "Default")
      (node (ref "P14") (pin "4") (pinfunction "4_4") (pintype "passive"))
      (node (ref "U2") (pin "20") (pinfunction "4Y2_20") (pintype "output"))
    )
    (net (code "24") (name "/Code7") (class "Default")
      (node (ref "J13") (pin "11") (pinfunction "11_11") (pintype "passive"))
      (node (ref "U2") (pin "27") (pinfunction "4A3_27") (pintype "input"))
    )
    (net (code "25") (name "/Code7_BufferOut") (class "Default")
      (node (ref "P14") (pin "5") (pinfunction "5_5") (pintype "passive"))
      (node (ref "U2") (pin "22") (pinfunction "4Y3_22") (pintype "output"))
    )
    (net (code "26") (name "/Code8") (class "Default")
      (node (ref "J13") (pin "9") (pinfunction "9_9") (pintype "passive"))
      (node (ref "U2") (pin "26") (pinfunction "4A4_26") (pintype "input"))
    )
    (net (code "27") (name "/Code8_BufferOut") (class "Default")
      (node (ref "P14") (pin "6") (pinfunction "6_6") (pintype "passive"))
      (node (ref "U2") (pin "23") (pinfunction "4Y4_23") (pintype "output"))
    )
    (net (code "28") (name "/EOC") (class "Default")
      (node (ref "J13") (pin "10") (pinfunction "10_10") (pintype "passive"))
      (node (ref "U2") (pin "38") (pinfunction "2A3_38") (pintype "input"))
    )
    (net (code "29") (name "/EOC_BufferOut") (class "Default")
      (node (ref "P3") (pin "2") (pinfunction "2_2") (pintype "passive"))
      (node (ref "U2") (pin "11") (pinfunction "2Y3_11") (pintype "output"))
    )
    (net (code "30") (name "/For_AVDD_ESD_1.5V") (class "Default")
      (node (ref "C12") (pin "2") (pinfunction "2_2") (pintype "passive"))
      (node (ref "R20") (pin "3") (pinfunction "CW_3") (pintype "passive"))
      (node (ref "U8") (pin "5") (pinfunction "OUT_5") (pintype "output"))
    )
    (net (code "31") (name "/For_AVDD_ESD_1V") (class "Default")
      (node (ref "J10") (pin "5") (pinfunction "5_5") (pintype "passive"))
      (node (ref "P9") (pin "2") (pinfunction "2_2") (pintype "passive"))
    )
    (net (code "32") (name "/For_DVDD_1.5V") (class "Default")
      (node (ref "C14") (pin "2") (pinfunction "2_2") (pintype "passive"))
      (node (ref "R19") (pin "3") (pinfunction "CW_3") (pintype "passive"))
      (node (ref "U7") (pin "5") (pinfunction "OUT_5") (pintype "output"))
    )
    (net (code "33") (name "/For_DVDD_1V") (class "Default")
      (node (ref "J13") (pin "3") (pinfunction "3_3") (pintype "passive"))
      (node (ref "P8") (pin "2") (pinfunction "2_2") (pintype "passive"))
    )
    (net (code "34") (name "/For_VCM_0.5V") (class "Default")
      (node (ref "J10") (pin "3") (pinfunction "3_3") (pintype "passive"))
      (node (ref "P10") (pin "2") (pinfunction "2_2") (pintype "passive"))
    )
    (net (code "35") (name "/For_VCM_1.5V") (class "Default")
      (node (ref "C16") (pin "2") (pinfunction "2_2") (pintype "passive"))
      (node (ref "R30") (pin "3") (pinfunction "CW_3") (pintype "passive"))
      (node (ref "U9") (pin "5") (pinfunction "OUT_5") (pintype "output"))
    )
    (net (code "36") (name "/IN_T12_N") (class "Default")
      (node (ref "J10") (pin "2") (pinfunction "2_2") (pintype "passive"))
      (node (ref "J9") (pin "2") (pinfunction "2_2") (pintype "passive"))
    )
    (net (code "37") (name "/IN_T12_P") (class "Default")
      (node (ref "J10") (pin "4") (pinfunction "4_4") (pintype "passive"))
      (node (ref "J12") (pin "2") (pinfunction "2_2") (pintype "passive"))
    )
    (net (code "38") (name "/LDO_OUT_2.5V") (class "Default")
      (node (ref "C29") (pin "1") (pinfunction "1_1") (pintype "passive"))
      (node (ref "P1") (pin "2") (pinfunction "2_2") (pintype "passive"))
      (node (ref "U11") (pin "5") (pinfunction "EN_5") (pintype "input"))
      (node (ref "U11") (pin "6") (pinfunction "IN_6") (pintype "power_in"))
    )
    (net (code "39") (name "/MUX0") (class "Default")
      (node (ref "J13") (pin "8") (pinfunction "8_8") (pintype "passive"))
      (node (ref "P7") (pin "1") (pinfunction "1_1") (pintype "passive"))
    )
    (net (code "40") (name "/MUX1") (class "Default")
      (node (ref "J13") (pin "7") (pinfunction "7_7") (pintype "passive"))
      (node (ref "P7") (pin "2") (pinfunction "2_2") (pintype "passive"))
    )
    (net (code "41") (name "/SEDE_0.5V") (class "Default")
      (node (ref "C25") (pin "1") (pinfunction "1_1") (pintype "passive"))
      (node (ref "TP4") (pin "1") (pinfunction "1_1") (pintype "passive"))
      (node (ref "U11") (pin "1") (pinfunction "OUT_1") (pintype "passive"))
      (node (ref "U11") (pin "2") (pinfunction "ADJ/SENSE_2") (pintype "passive"))
      (node (ref "U5") (pin "2") (pinfunction "VOCM_2") (pintype "power_in"))
    )
    (net (code "42") (name "/SEDE_INPUT") (class "Default")
      (node (ref "P12") (pin "1") (pinfunction "1_1") (pintype "passive"))
      (node (ref "R22") (pin "1") (pinfunction "1_1") (pintype "passive"))
      (node (ref "TP3") (pin "1") (pinfunction "1_1") (pintype "passive"))
    )
    (net (code "43") (name "/VDD_2.5V") (class "Default")
      (node (ref "C11") (pin "2") (pinfunction "2_2") (pintype "passive"))
      (node (ref "C13") (pin "2") (pinfunction "2_2") (pintype "passive"))
      (node (ref "C15") (pin "2") (pinfunction "2_2") (pintype "passive"))
      (node (ref "C2") (pin "1") (pinfunction "1_1") (pintype "passive"))
      (node (ref "C4") (pin "1") (pinfunction "1_1") (pintype "passive"))
      (node (ref "J13") (pin "1") (pinfunction "1_1") (pintype "passive"))
      (node (ref "J3") (pin "1") (pinfunction "1_1") (pintype "passive"))
      (node (ref "U7") (pin "1") (pinfunction "IN_1") (pintype "input"))
      (node (ref "U7") (pin "3") (pinfunction "EN_3") (pintype "input"))
      (node (ref "U8") (pin "1") (pinfunction "IN_1") (pintype "input"))
      (node (ref "U8") (pin "3") (pinfunction "EN_3") (pintype "input"))
      (node (ref "U9") (pin "1") (pinfunction "IN_1") (pintype "input"))
      (node (ref "U9") (pin "3") (pinfunction "EN_3") (pintype "input"))
    )
    (net (code "44") (name "/V_SIN_IN_N") (class "Default")
      (node (ref "J11") (pin "1") (pinfunction "1_1") (pintype "passive"))
      (node (ref "J9") (pin "1") (pinfunction "1_1") (pintype "passive"))
      (node (ref "R28") (pin "2") (pinfunction "2_2") (pintype "passive"))
    )
    (net (code "45") (name "/V_SIN_IN_P") (class "Default")
      (node (ref "C17") (pin "1") (pinfunction "1_1") (pintype "passive"))
      (node (ref "J12") (pin "3") (pinfunction "3_3") (pintype "passive"))
      (node (ref "J2") (pin "1") (pinfunction "1_1") (pintype "passive"))
      (node (ref "R17") (pin "1") (pinfunction "1_1") (pintype "passive"))
      (node (ref "TP1") (pin "1") (pinfunction "1_1") (pintype "passive"))
    )
    (net (code "46") (name "2.5V_Buffer") (class "Default")
      (node (ref "C28") (pin "2") (pinfunction "2_2") (pintype "passive"))
      (node (ref "C9") (pin "2") (pinfunction "2_2") (pintype "passive"))
      (node (ref "U1") (pin "5") (pinfunction "VOUT_5") (pintype "power_in"))
      (node (ref "U2") (pin "1") (pinfunction "1~{OE}_1") (pintype "input"))
      (node (ref "U2") (pin "18") (pinfunction "VCC_18") (pintype "power_in"))
      (node (ref "U2") (pin "31") (pinfunction "VCC_31") (pintype "open_emitter"))
      (node (ref "U2") (pin "42") (pinfunction "VCC_42") (pintype "power_in"))
      (node (ref "U2") (pin "7") (pinfunction "VCC_7") (pintype "power_in"))
    )
    (net (code "47") (name "AGND") (class "Default")
      (node (ref "C11") (pin "1") (pinfunction "1_1") (pintype "passive"))
      (node (ref "C12") (pin "1") (pinfunction "1_1") (pintype "passive"))
      (node (ref "C13") (pin "1") (pinfunction "1_1") (pintype "passive"))
      (node (ref "C14") (pin "1") (pinfunction "1_1") (pintype "passive"))
      (node (ref "C15") (pin "1") (pinfunction "1_1") (pintype "passive"))
      (node (ref "C16") (pin "1") (pinfunction "1_1") (pintype "passive"))
      (node (ref "C2") (pin "2") (pinfunction "2_2") (pintype "passive"))
      (node (ref "C4") (pin "2") (pinfunction "2_2") (pintype "passive"))
      (node (ref "J10") (pin "1") (pinfunction "1_1") (pintype "passive"))
      (node (ref "J13") (pin "2") (pinfunction "2_2") (pintype "passive"))
      (node (ref "J13") (pin "4") (pinfunction "4_4") (pintype "passive"))
      (node (ref "J4") (pin "1") (pinfunction "1_1") (pintype "passive"))
      (node (ref "P2") (pin "1") (pinfunction "1_1") (pintype "passive"))
      (node (ref "P2") (pin "2") (pinfunction "2_2") (pintype "passive"))
      (node (ref "P5") (pin "1") (pinfunction "1_1") (pintype "passive"))
      (node (ref "P5") (pin "2") (pinfunction "2_2") (pintype "passive"))
      (node (ref "R18") (pin "1") (pinfunction "1_1") (pintype "passive"))
      (node (ref "R19") (pin "1") (pinfunction "CCW_1") (pintype "passive"))
      (node (ref "R20") (pin "1") (pinfunction "CCW_1") (pintype "passive"))
      (node (ref "R21") (pin "2") (pinfunction "2_2") (pintype "passive"))
      (node (ref "R23") (pin "2") (pinfunction "2_2") (pintype "passive"))
      (node (ref "R30") (pin "1") (pinfunction "CCW_1") (pintype "passive"))
      (node (ref "R31") (pin "2") (pinfunction "2_2") (pintype "passive"))
      (node (ref "U7") (pin "2") (pinfunction "GND_2") (pintype "power_in"))
      (node (ref "U8") (pin "2") (pinfunction "GND_2") (pintype "power_in"))
      (node (ref "U9") (pin "2") (pinfunction "GND_2") (pintype "power_in"))
    )
    (net (code "48") (name "DGND") (class "Default")
      (node (ref "C1") (pin "2") (pinfunction "2_2") (pintype "passive"))
      (node (ref "C10") (pin "2") (pinfunction "2_2") (pintype "passive"))
      (node (ref "C18") (pin "2") (pinfunction "2_2") (pintype "passive"))
      (node (ref "C19") (pin "2") (pinfunction "2_2") (pintype "passive"))
      (node (ref "C20") (pin "2") (pinfunction "2_2") (pintype "passive"))
      (node (ref "C21") (pin "2") (pinfunction "2_2") (pintype "passive"))
      (node (ref "C22") (pin "1") (pinfunction "1_1") (pintype "passive"))
      (node (ref "C23") (pin "2") (pinfunction "2_2") (pintype "passive"))
      (node (ref "C24") (pin "1") (pinfunction "1_1") (pintype "passive"))
      (node (ref "C25") (pin "2") (pinfunction "2_2") (pintype "passive"))
      (node (ref "C27") (pin "1") (pinfunction "1_1") (pintype "passive"))
      (node (ref "C28") (pin "1") (pinfunction "1_1") (pintype "passive"))
      (node (ref "C29") (pin "2") (pinfunction "2_2") (pintype "passive"))
      (node (ref "C3") (pin "2") (pinfunction "2_2") (pintype "passive"))
      (node (ref "C5") (pin "2") (pinfunction "2_2") (pintype "passive"))
      (node (ref "C6") (pin "2") (pinfunction "2_2") (pintype "passive"))
      (node (ref "C7") (pin "1") (pinfunction "1_1") (pintype "passive"))
      (node (ref "C8") (pin "1") (pinfunction "1_1") (pintype "passive"))
      (node (ref "C9") (pin "1") (pinfunction "1_1") (pintype "passive"))
      (node (ref "J5") (pin "1") (pinfunction "1_1") (pintype "passive"))
      (node (ref "J8") (pin "1") (pinfunction "1_1") (pintype "passive"))
      (node (ref "P11") (pin "1") (pinfunction "1_1") (pintype "passive"))
      (node (ref "P11") (pin "2") (pinfunction "2_2") (pintype "passive"))
      (node (ref "P13") (pin "1") (pinfunction "1_1") (pintype "passive"))
      (node (ref "P13") (pin "2") (pinfunction "2_2") (pintype "passive"))
      (node (ref "P3") (pin "6") (pinfunction "6_6") (pintype "passive"))
      (node (ref "P6") (pin "1") (pinfunction "1_1") (pintype "passive"))
      (node (ref "P6") (pin "2") (pinfunction "2_2") (pintype "passive"))
      (node (ref "R1") (pin "2") (pinfunction "2_2") (pintype "passive"))
      (node (ref "R17") (pin "2") (pinfunction "2_2") (pintype "passive"))
      (node (ref "R18") (pin "2") (pinfunction "2_2") (pintype "passive"))
      (node (ref "R27") (pin "1") (pinfunction "1_1") (pintype "passive"))
      (node (ref "R28") (pin "1") (pinfunction "1_1") (pintype "passive"))
      (node (ref "U1") (pin "2") (pinfunction "GND_2") (pintype "power_in"))
      (node (ref "U10") (pin "1") (pinfunction "GND_1") (pintype "power_in"))
      (node (ref "U10") (pin "3") (pinfunction "GND_3") (pintype "power_in"))
      (node (ref "U11") (pin "3") (pinfunction "GND_3") (pintype "power_in"))
      (node (ref "U11") (pin "7") (pinfunction "GND_7") (pintype "power_in"))
      (node (ref "U2") (pin "10") (pinfunction "GND_10") (pintype "power_in"))
      (node (ref "U2") (pin "15") (pinfunction "GND_15") (pintype "power_in"))
      (node (ref "U2") (pin "21") (pinfunction "GND_21") (pintype "power_in"))
      (node (ref "U2") (pin "24") (pinfunction "4~{OE}_24") (pintype "input"))
      (node (ref "U2") (pin "25") (pinfunction "3~{OE}_25") (pintype "input"))
      (node (ref "U2") (pin "28") (pinfunction "GND_28") (pintype "power_in"))
      (node (ref "U2") (pin "34") (pinfunction "GND_34") (pintype "power_in"))
      (node (ref "U2") (pin "39") (pinfunction "GND_39") (pintype "power_in"))
      (node (ref "U2") (pin "4") (pinfunction "GND_4") (pintype "power_in"))
      (node (ref "U2") (pin "41") (pinfunction "2A1_41") (pintype "input"))
      (node (ref "U2") (pin "43") (pinfunction "1A4_43") (pintype "input"))
      (node (ref "U2") (pin "44") (pinfunction "1A3_44") (pintype "input"))
      (node (ref "U2") (pin "45") (pinfunction "GND_45") (pintype "power_in"))
      (node (ref "U2") (pin "46") (pinfunction "1A2_46") (pintype "input"))
      (node (ref "U2") (pin "47") (pinfunction "1A1_47") (pintype "input"))
      (node (ref "U2") (pin "48") (pinfunction "2~{OE}_48") (pintype "input"))
      (node (ref "U3") (pin "2") (pinfunction "GND_2") (pintype "power_in"))
    )
    (net (code "49") (name "Net-(P4-Pad1)") (class "Default")
      (node (ref "P4") (pin "1") (pinfunction "1_1") (pintype "passive"))
      (node (ref "R6") (pin "2") (pinfunction "2_2") (pintype "passive"))
      (node (ref "TP2") (pin "1") (pinfunction "1_1") (pintype "passive"))
    )
    (net (code "50") (name "Net-(R19-WIPER)") (class "Default")
      (node (ref "P8") (pin "1") (pinfunction "1_1") (pintype "passive"))
      (node (ref "R19") (pin "2") (pinfunction "WIPER_2") (pintype "passive"))
      (node (ref "R21") (pin "1") (pinfunction "1_1") (pintype "passive"))
    )
    (net (code "51") (name "Net-(R20-WIPER)") (class "Default")
      (node (ref "P9") (pin "1") (pinfunction "1_1") (pintype "passive"))
      (node (ref "R20") (pin "2") (pinfunction "WIPER_2") (pintype "passive"))
      (node (ref "R23") (pin "1") (pinfunction "1_1") (pintype "passive"))
    )
    (net (code "52") (name "Net-(R30-WIPER)") (class "Default")
      (node (ref "P10") (pin "1") (pinfunction "1_1") (pintype "passive"))
      (node (ref "R30") (pin "2") (pinfunction "WIPER_2") (pintype "passive"))
      (node (ref "R31") (pin "1") (pinfunction "1_1") (pintype "passive"))
    )
    (net (code "53") (name "Net-(U3-VOUT)") (class "Default")
      (node (ref "C7") (pin "2") (pinfunction "2_2") (pintype "passive"))
      (node (ref "P1") (pin "1") (pinfunction "1_1") (pintype "passive"))
      (node (ref "U3") (pin "5") (pinfunction "VOUT_5") (pintype "power_in"))
    )
    (net (code "54") (name "Net-(U4--IN)") (class "Default")
      (node (ref "P12") (pin "2") (pinfunction "2_2") (pintype "passive"))
      (node (ref "U4") (pin "2") (pinfunction "-IN_2") (pintype "input"))
      (node (ref "U4") (pin "6") (pinfunction "VOUT_6") (pintype "output"))
    )
    (net (code "55") (name "Net-(U10-0.5fC{slash}*fC)") (class "Default")
      (node (ref "J14") (pin "2") (pinfunction "2_2") (pintype "passive"))
      (node (ref "U10") (pin "5") (pinfunction "0.5fC/*fC_5") (pintype "passive"))
    )
    (net (code "56") (name "Net-(U10-VIN)") (class "Default")
      (node (ref "C17") (pin "2") (pinfunction "2_2") (pintype "passive"))
      (node (ref "U10") (pin "2") (pinfunction "VIN_2") (pintype "input"))
    )
    (net (code "57") (name "Net-(U10-VOUT)") (class "Default")
      (node (ref "R6") (pin "1") (pinfunction "1_1") (pintype "passive"))
      (node (ref "U10") (pin "8") (pinfunction "VOUT_8") (pintype "output"))
    )
    (net (code "58") (name "unconnected-(J1-MNT_1-Pad2)") (class "Default")
      (node (ref "J1") (pin "2") (pinfunction "MNT_1_2") (pintype "passive+no_connect"))
    )
    (net (code "59") (name "unconnected-(J1-MNT_2-Pad3)") (class "Default")
      (node (ref "J1") (pin "3") (pinfunction "MNT_2_3") (pintype "passive+no_connect"))
    )
    (net (code "60") (name "unconnected-(J1-MNT_3-Pad4)") (class "Default")
      (node (ref "J1") (pin "4") (pinfunction "MNT_3_4") (pintype "passive+no_connect"))
    )
    (net (code "61") (name "unconnected-(J1-MNT_4-Pad5)") (class "Default")
      (node (ref "J1") (pin "5") (pinfunction "MNT_4_5") (pintype "passive+no_connect"))
    )
    (net (code "62") (name "unconnected-(J2-MNT_1-Pad2)") (class "Default")
      (node (ref "J2") (pin "2") (pinfunction "MNT_1_2") (pintype "passive+no_connect"))
    )
    (net (code "63") (name "unconnected-(J2-MNT_2-Pad3)") (class "Default")
      (node (ref "J2") (pin "3") (pinfunction "MNT_2_3") (pintype "passive+no_connect"))
    )
    (net (code "64") (name "unconnected-(J2-MNT_3-Pad4)") (class "Default")
      (node (ref "J2") (pin "4") (pinfunction "MNT_3_4") (pintype "passive+no_connect"))
    )
    (net (code "65") (name "unconnected-(J2-MNT_4-Pad5)") (class "Default")
      (node (ref "J2") (pin "5") (pinfunction "MNT_4_5") (pintype "passive+no_connect"))
    )
    (net (code "66") (name "unconnected-(J3-MNT_1-Pad2)") (class "Default")
      (node (ref "J3") (pin "2") (pinfunction "MNT_1_2") (pintype "passive+no_connect"))
    )
    (net (code "67") (name "unconnected-(J3-MNT_2-Pad3)") (class "Default")
      (node (ref "J3") (pin "3") (pinfunction "MNT_2_3") (pintype "passive+no_connect"))
    )
    (net (code "68") (name "unconnected-(J3-MNT_3-Pad4)") (class "Default")
      (node (ref "J3") (pin "4") (pinfunction "MNT_3_4") (pintype "passive+no_connect"))
    )
    (net (code "69") (name "unconnected-(J3-MNT_4-Pad5)") (class "Default")
      (node (ref "J3") (pin "5") (pinfunction "MNT_4_5") (pintype "passive+no_connect"))
    )
    (net (code "70") (name "unconnected-(J4-MNT_1-Pad2)") (class "Default")
      (node (ref "J4") (pin "2") (pinfunction "MNT_1_2") (pintype "passive+no_connect"))
    )
    (net (code "71") (name "unconnected-(J4-MNT_2-Pad3)") (class "Default")
      (node (ref "J4") (pin "3") (pinfunction "MNT_2_3") (pintype "passive+no_connect"))
    )
    (net (code "72") (name "unconnected-(J4-MNT_3-Pad4)") (class "Default")
      (node (ref "J4") (pin "4") (pinfunction "MNT_3_4") (pintype "passive+no_connect"))
    )
    (net (code "73") (name "unconnected-(J4-MNT_4-Pad5)") (class "Default")
      (node (ref "J4") (pin "5") (pinfunction "MNT_4_5") (pintype "passive+no_connect"))
    )
    (net (code "74") (name "unconnected-(J5-MNT_1-Pad2)") (class "Default")
      (node (ref "J5") (pin "2") (pinfunction "MNT_1_2") (pintype "passive+no_connect"))
    )
    (net (code "75") (name "unconnected-(J5-MNT_2-Pad3)") (class "Default")
      (node (ref "J5") (pin "3") (pinfunction "MNT_2_3") (pintype "passive+no_connect"))
    )
    (net (code "76") (name "unconnected-(J5-MNT_3-Pad4)") (class "Default")
      (node (ref "J5") (pin "4") (pinfunction "MNT_3_4") (pintype "passive+no_connect"))
    )
    (net (code "77") (name "unconnected-(J5-MNT_4-Pad5)") (class "Default")
      (node (ref "J5") (pin "5") (pinfunction "MNT_4_5") (pintype "passive+no_connect"))
    )
    (net (code "78") (name "unconnected-(J6-MNT_1-Pad2)") (class "Default")
      (node (ref "J6") (pin "2") (pinfunction "MNT_1_2") (pintype "passive+no_connect"))
    )
    (net (code "79") (name "unconnected-(J6-MNT_2-Pad3)") (class "Default")
      (node (ref "J6") (pin "3") (pinfunction "MNT_2_3") (pintype "passive+no_connect"))
    )
    (net (code "80") (name "unconnected-(J6-MNT_3-Pad4)") (class "Default")
      (node (ref "J6") (pin "4") (pinfunction "MNT_3_4") (pintype "passive+no_connect"))
    )
    (net (code "81") (name "unconnected-(J6-MNT_4-Pad5)") (class "Default")
      (node (ref "J6") (pin "5") (pinfunction "MNT_4_5") (pintype "passive+no_connect"))
    )
    (net (code "82") (name "unconnected-(J7-MNT_1-Pad2)") (class "Default")
      (node (ref "J7") (pin "2") (pinfunction "MNT_1_2") (pintype "passive+no_connect"))
    )
    (net (code "83") (name "unconnected-(J7-MNT_2-Pad3)") (class "Default")
      (node (ref "J7") (pin "3") (pinfunction "MNT_2_3") (pintype "passive+no_connect"))
    )
    (net (code "84") (name "unconnected-(J7-MNT_3-Pad4)") (class "Default")
      (node (ref "J7") (pin "4") (pinfunction "MNT_3_4") (pintype "passive+no_connect"))
    )
    (net (code "85") (name "unconnected-(J7-MNT_4-Pad5)") (class "Default")
      (node (ref "J7") (pin "5") (pinfunction "MNT_4_5") (pintype "passive+no_connect"))
    )
    (net (code "86") (name "unconnected-(J8-MNT_1-Pad2)") (class "Default")
      (node (ref "J8") (pin "2") (pinfunction "MNT_1_2") (pintype "passive+no_connect"))
    )
    (net (code "87") (name "unconnected-(J8-MNT_2-Pad3)") (class "Default")
      (node (ref "J8") (pin "3") (pinfunction "MNT_2_3") (pintype "passive+no_connect"))
    )
    (net (code "88") (name "unconnected-(J8-MNT_3-Pad4)") (class "Default")
      (node (ref "J8") (pin "4") (pinfunction "MNT_3_4") (pintype "passive+no_connect"))
    )
    (net (code "89") (name "unconnected-(J8-MNT_4-Pad5)") (class "Default")
      (node (ref "J8") (pin "5") (pinfunction "MNT_4_5") (pintype "passive+no_connect"))
    )
    (net (code "90") (name "unconnected-(J11-MNT_1-Pad2)") (class "Default")
      (node (ref "J11") (pin "2") (pinfunction "MNT_1_2") (pintype "passive+no_connect"))
    )
    (net (code "91") (name "unconnected-(J11-MNT_2-Pad3)") (class "Default")
      (node (ref "J11") (pin "3") (pinfunction "MNT_2_3") (pintype "passive+no_connect"))
    )
    (net (code "92") (name "unconnected-(J11-MNT_3-Pad4)") (class "Default")
      (node (ref "J11") (pin "4") (pinfunction "MNT_3_4") (pintype "passive+no_connect"))
    )
    (net (code "93") (name "unconnected-(J11-MNT_4-Pad5)") (class "Default")
      (node (ref "J11") (pin "5") (pinfunction "MNT_4_5") (pintype "passive+no_connect"))
    )
    (net (code "94") (name "unconnected-(U1-NC-Pad4)") (class "Default")
      (node (ref "U1") (pin "4") (pinfunction "NC_4") (pintype "passive+no_connect"))
    )
    (net (code "95") (name "unconnected-(U2-1Y1-Pad2)") (class "Default")
      (node (ref "U2") (pin "2") (pinfunction "1Y1_2") (pintype "output+no_connect"))
    )
    (net (code "96") (name "unconnected-(U2-1Y2-Pad3)") (class "Default")
      (node (ref "U2") (pin "3") (pinfunction "1Y2_3") (pintype "output+no_connect"))
    )
    (net (code "97") (name "unconnected-(U2-1Y3-Pad5)") (class "Default")
      (node (ref "U2") (pin "5") (pinfunction "1Y3_5") (pintype "output+no_connect"))
    )
    (net (code "98") (name "unconnected-(U2-1Y4-Pad6)") (class "Default")
      (node (ref "U2") (pin "6") (pinfunction "1Y4_6") (pintype "output+no_connect"))
    )
    (net (code "99") (name "unconnected-(U2-2Y1-Pad8)") (class "Default")
      (node (ref "U2") (pin "8") (pinfunction "2Y1_8") (pintype "output+no_connect"))
    )
    (net (code "100") (name "unconnected-(U3-NC-Pad4)") (class "Default")
      (node (ref "U3") (pin "4") (pinfunction "NC_4") (pintype "passive+no_connect"))
    )
    (net (code "101") (name "unconnected-(U4-NC-Pad5)") (class "Default")
      (node (ref "U4") (pin "5") (pinfunction "NC_5") (pintype "passive+no_connect"))
    )
    (net (code "102") (name "unconnected-(U4-NULL-Pad1)") (class "Default")
      (node (ref "U4") (pin "1") (pinfunction "NULL_1") (pintype "input+no_connect"))
    )
    (net (code "103") (name "unconnected-(U4-NULL-Pad8)") (class "Default")
      (node (ref "U4") (pin "8") (pinfunction "NULL_8") (pintype "input+no_connect"))
    )
    (net (code "104") (name "unconnected-(U5-~{DISABLE}-Pad7)") (class "Default")
      (node (ref "U5") (pin "7") (pinfunction "~{DISABLE}_7") (pintype "passive+no_connect"))
    )
    (net (code "105") (name "unconnected-(U7-NC{slash}FB-Pad4)") (class "Default")
      (node (ref "U7") (pin "4") (pinfunction "NC/FB_4") (pintype "passive+no_connect"))
    )
    (net (code "106") (name "unconnected-(U8-NC{slash}FB-Pad4)") (class "Default")
      (node (ref "U8") (pin "4") (pinfunction "NC/FB_4") (pintype "passive+no_connect"))
    )
    (net (code "107") (name "unconnected-(U9-NC{slash}FB-Pad4)") (class "Default")
      (node (ref "U9") (pin "4") (pinfunction "NC/FB_4") (pintype "passive+no_connect"))
    )
    (net (code "108") (name "unconnected-(U11-PG-Pad4)") (class "Default")
      (node (ref "U11") (pin "4") (pinfunction "PG_4") (pintype "output+no_connect"))
    )
  )
)
